# main.net
KiCad netlist of a schematic drawn in EAGLE
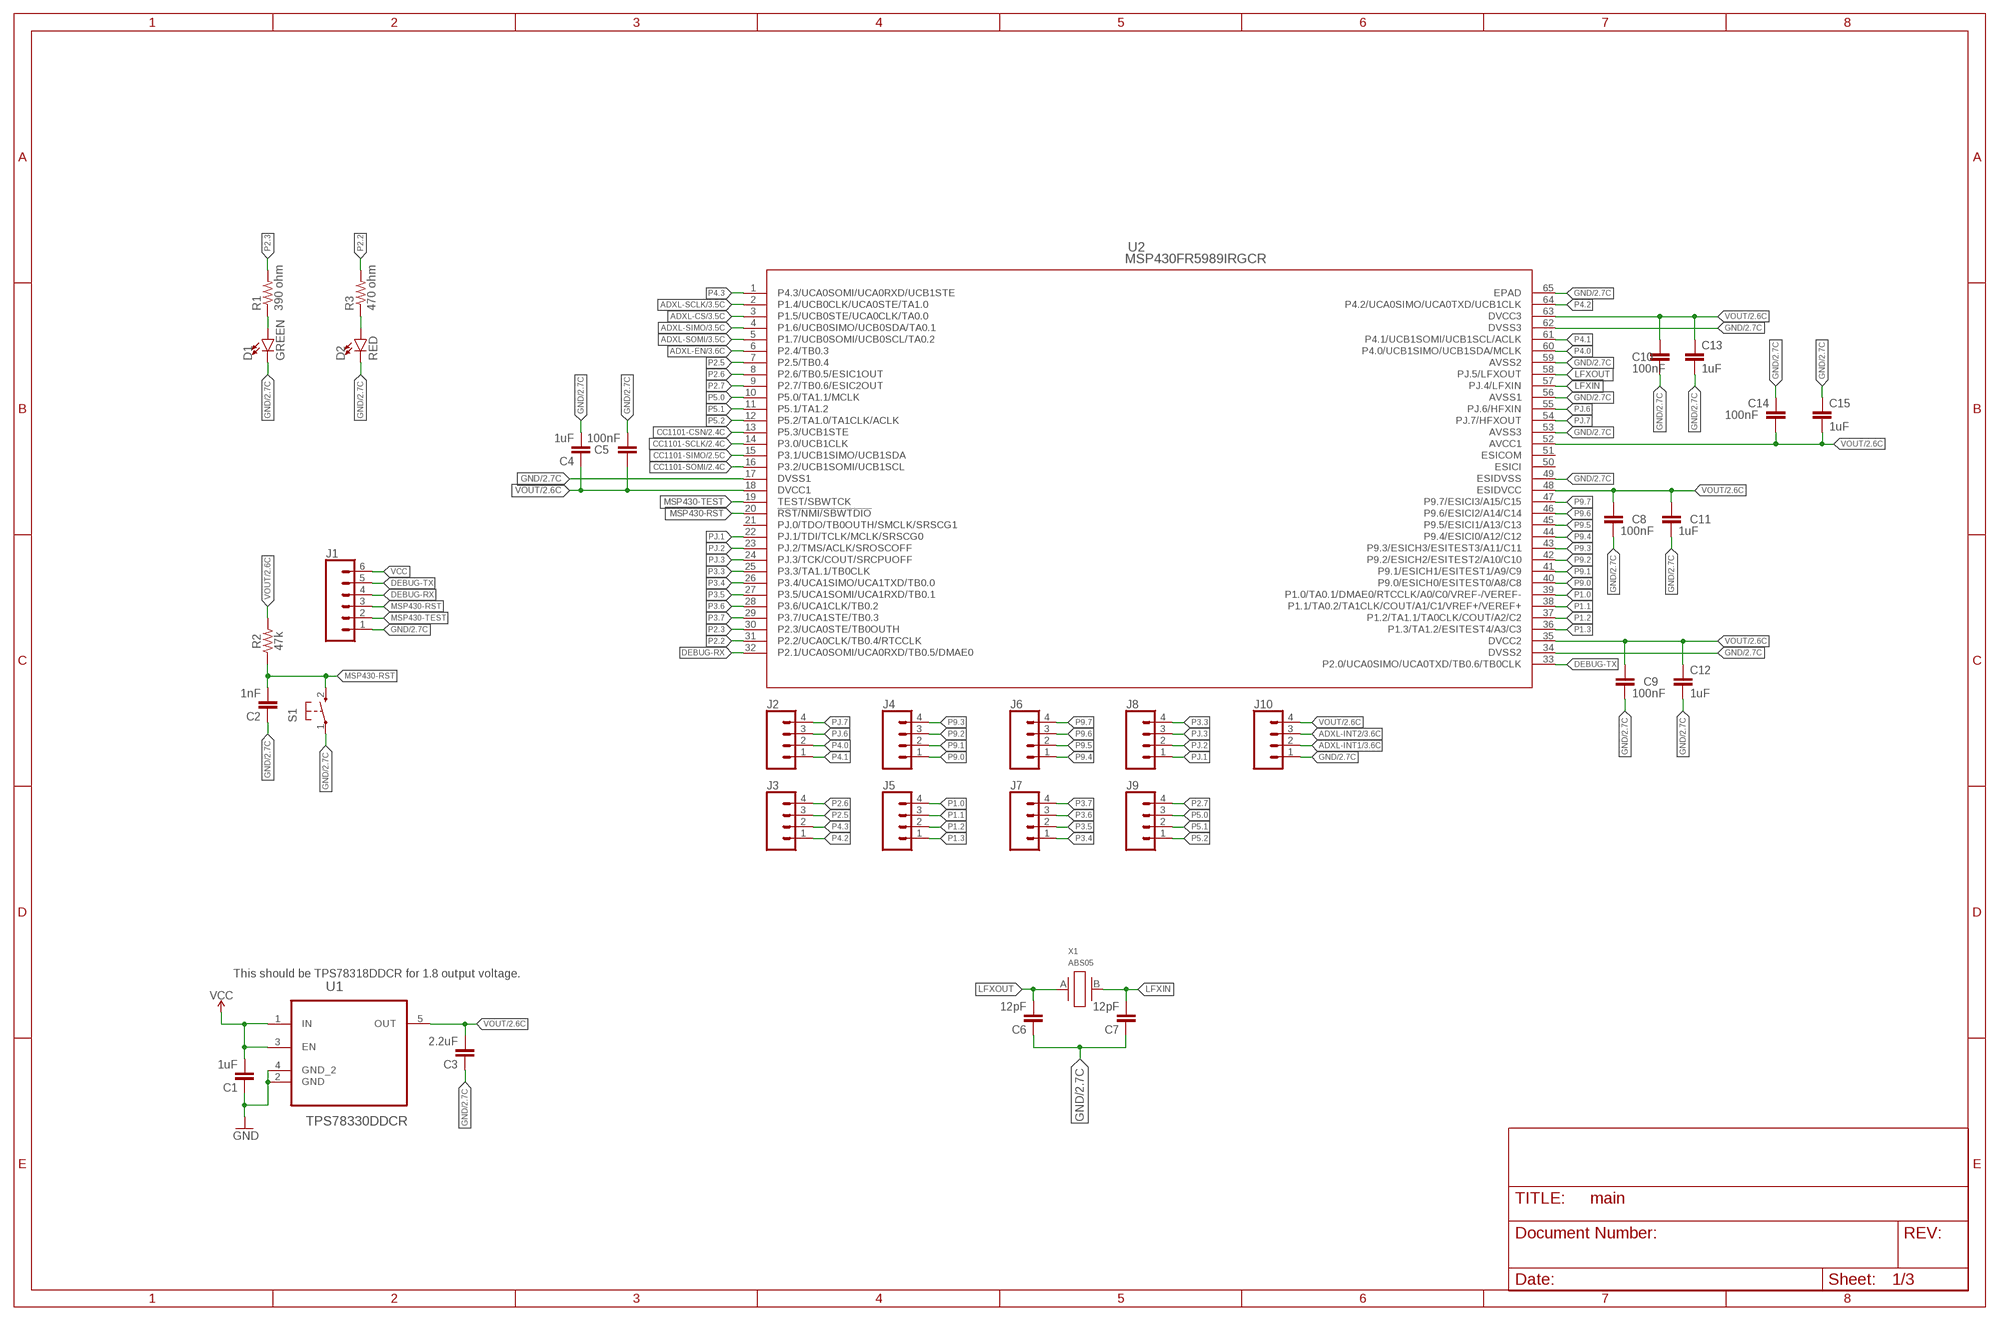
[diagram p0: schematic, sheet 1]
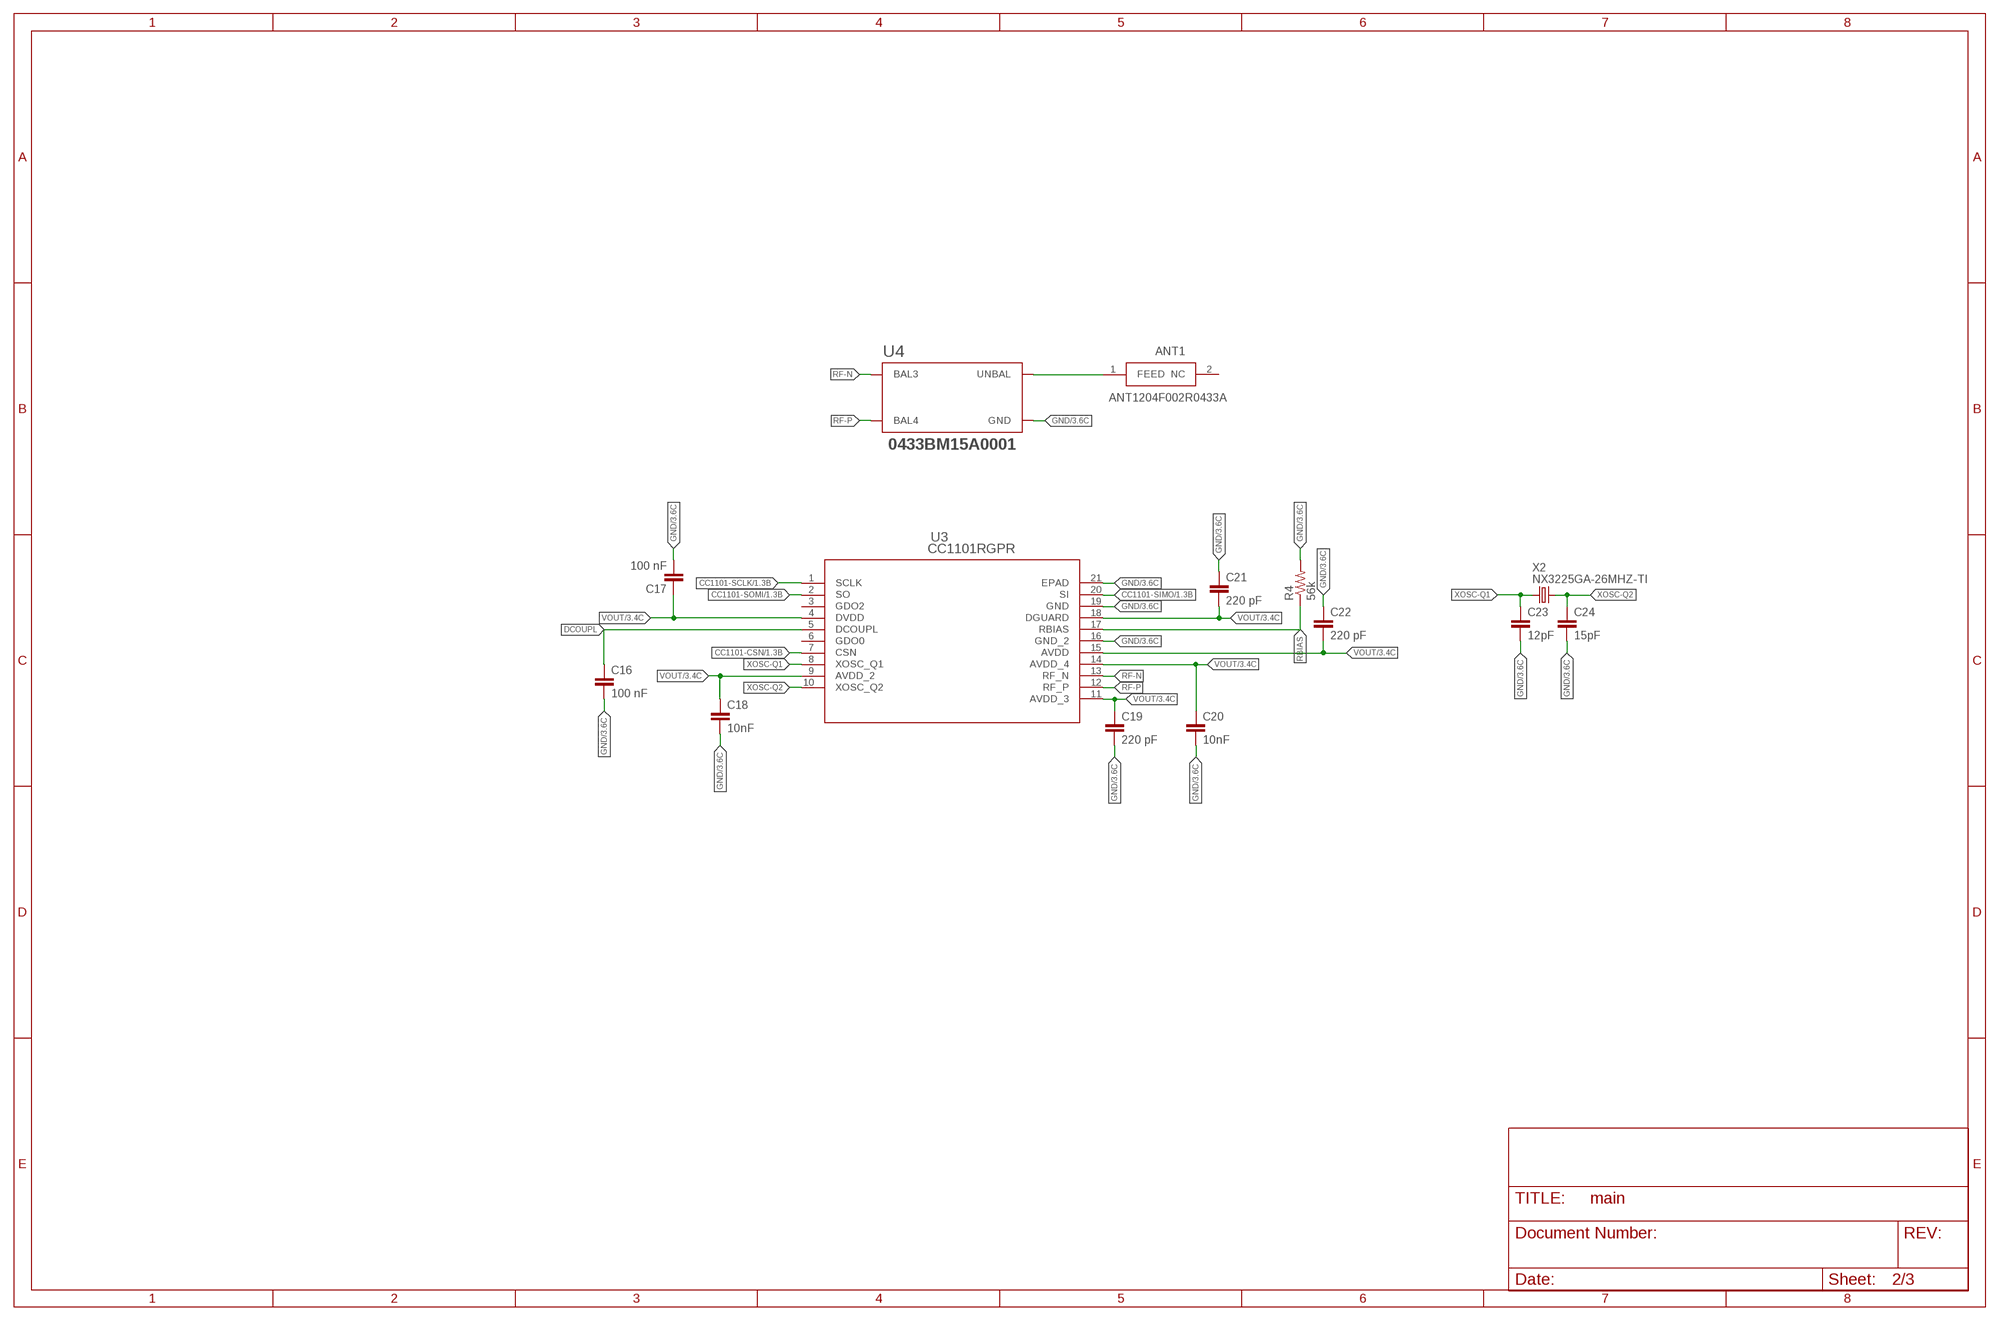
[diagram p1: schematic, sheet 2]
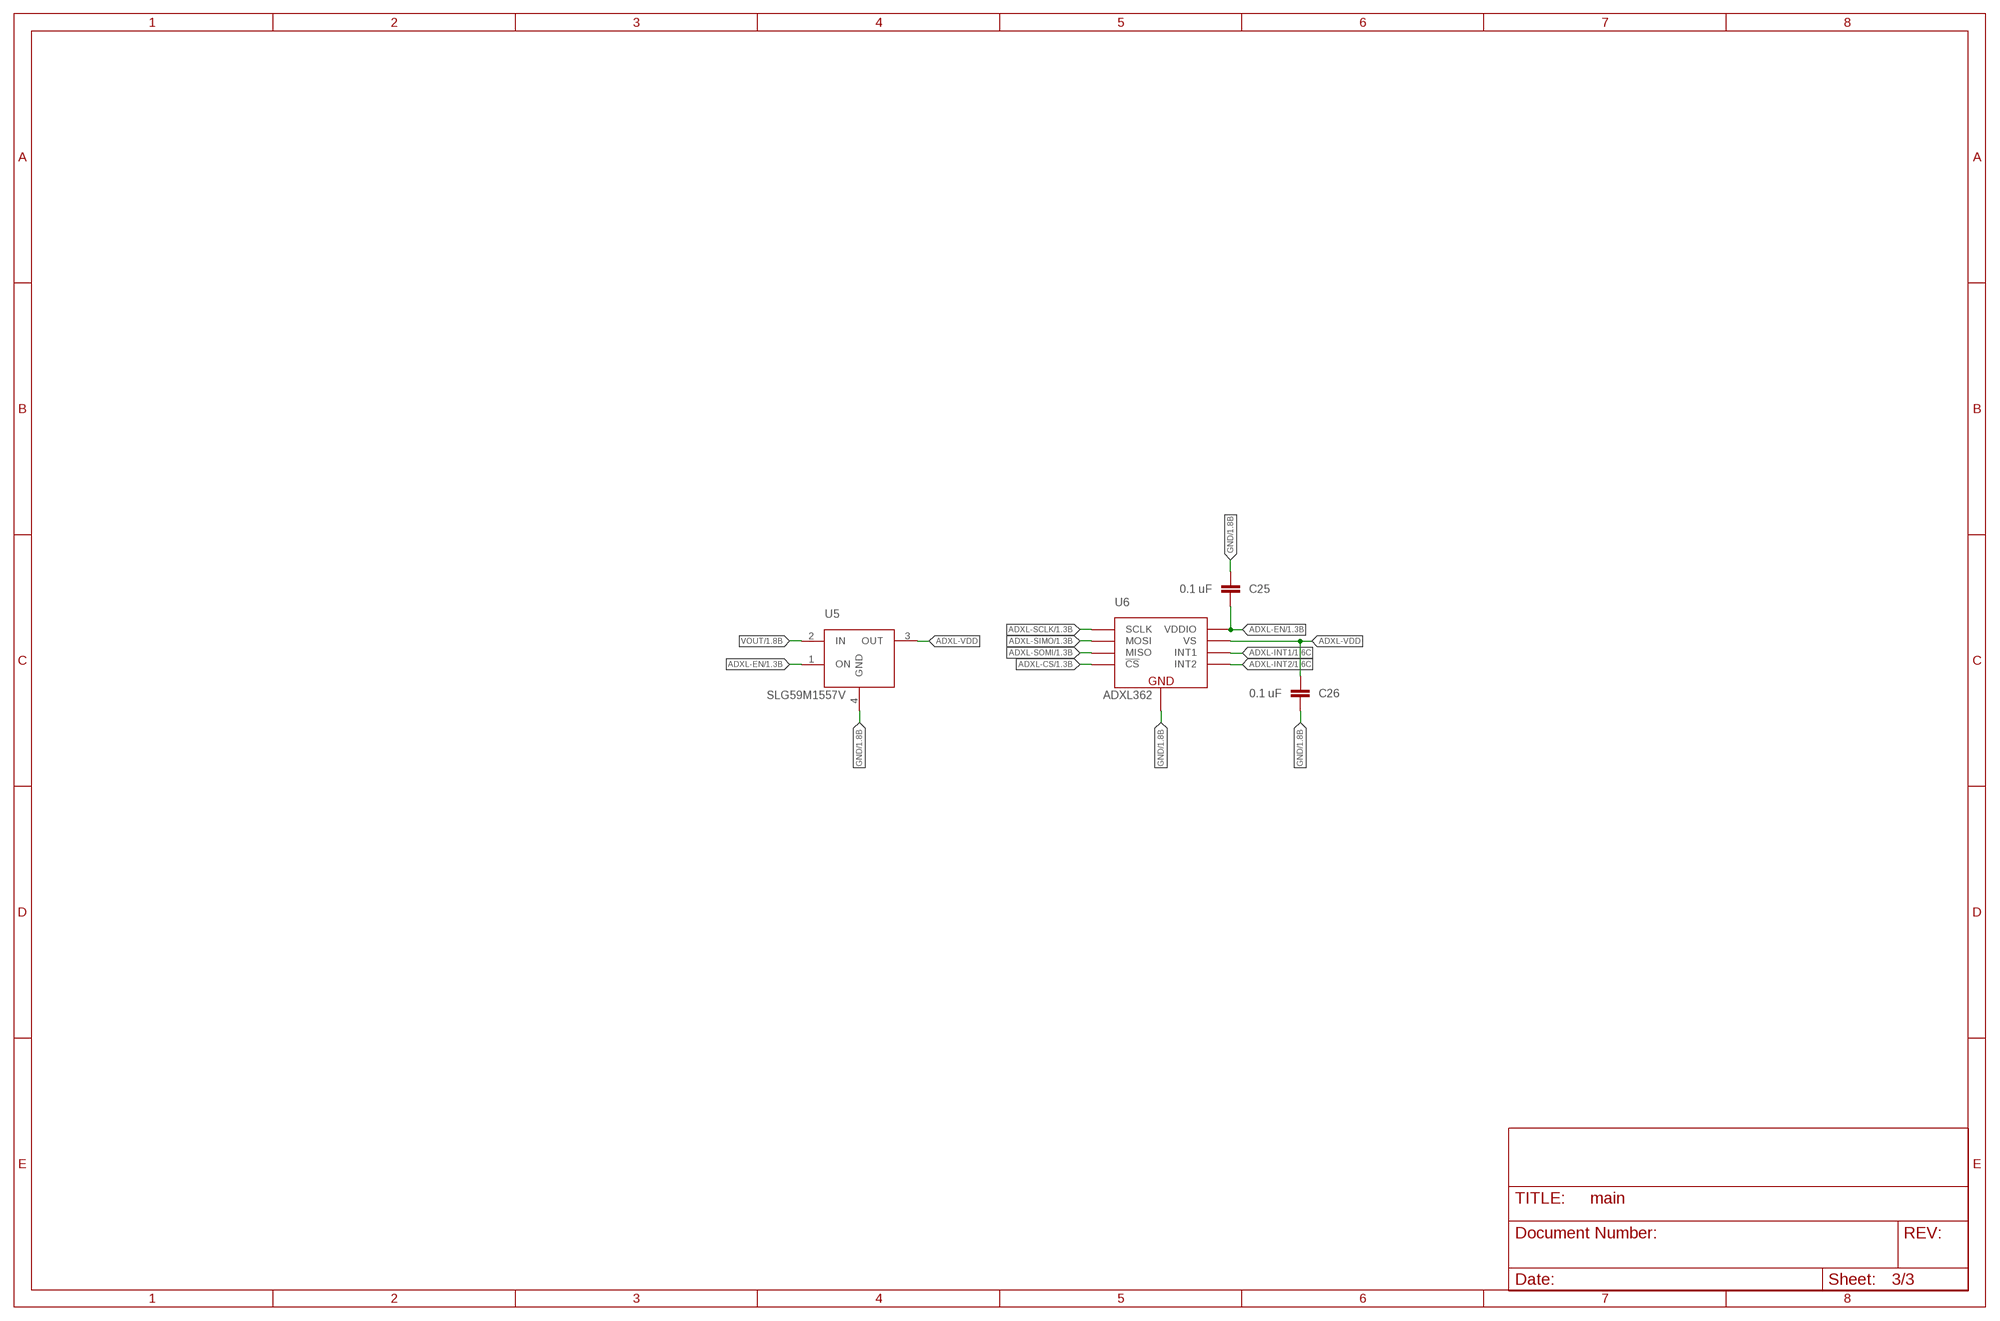
[diagram p2: schematic, sheet 3]

(export (version "E")
  (design (tool "Eeschema 10.0.6"))
  (components
    (comp (ref "C1")
      (value "1uF")
      (footprint "eagle-import:0603")
      (libsource (lib "eagle-import") (part "C-EU0603"))
    )
    (comp (ref "C2")
      (value "1nF")
      (footprint "eagle-import:0603")
      (libsource (lib "eagle-import") (part "C-EU0603"))
    )
    (comp (ref "C3")
      (value "2.2uF")
      (footprint "eagle-import:0603")
      (libsource (lib "eagle-import") (part "C-EU0603"))
    )
    (comp (ref "C4")
      (value "1uF")
      (footprint "eagle-import:0603")
      (libsource (lib "eagle-import") (part "C-EU0603"))
    )
    (comp (ref "C5")
      (value "100nF")
      (footprint "eagle-import:0603")
      (libsource (lib "eagle-import") (part "C-EU0603"))
    )
    (comp (ref "C6")
      (value "12pF")
      (footprint "eagle-import:0603")
      (fields (field (name "MPN") "CL10C120JB8NNNC"))
      (libsource (lib "eagle-import") (part "C-EU0603"))
    )
    (comp (ref "C7")
      (value "12pF")
      (footprint "eagle-import:0603")
      (fields (field (name "MPN") "CL10C120JB8NNNC"))
      (libsource (lib "eagle-import") (part "C-EU0603"))
    )
    (comp (ref "C8")
      (value "100nF")
      (footprint "eagle-import:0603")
      (libsource (lib "eagle-import") (part "C-EU0603"))
    )
    (comp (ref "C9")
      (value "100nF")
      (footprint "eagle-import:0603")
      (libsource (lib "eagle-import") (part "C-EU0603"))
    )
    (comp (ref "C10")
      (value "100nF")
      (footprint "eagle-import:0603")
      (libsource (lib "eagle-import") (part "C-EU0603"))
    )
    (comp (ref "C11")
      (value "1uF")
      (footprint "eagle-import:0603")
      (libsource (lib "eagle-import") (part "C-EU0603"))
    )
    (comp (ref "C12")
      (value "1uF")
      (footprint "eagle-import:0603")
      (libsource (lib "eagle-import") (part "C-EU0603"))
    )
    (comp (ref "C13")
      (value "1uF")
      (footprint "eagle-import:0603")
      (libsource (lib "eagle-import") (part "C-EU0603"))
    )
    (comp (ref "C14")
      (value "100nF")
      (footprint "eagle-import:0603")
      (libsource (lib "eagle-import") (part "C-EU0603"))
    )
    (comp (ref "C15")
      (value "1uF")
      (footprint "eagle-import:0603")
      (libsource (lib "eagle-import") (part "C-EU0603"))
    )
    (comp (ref "D1")
      (value "GREEN")
      (footprint "eagle-import:LED-0603")
      (libsource (lib "eagle-import") (part "LED-GREEN0603"))
    )
    (comp (ref "D2")
      (value "RED")
      (footprint "eagle-import:LED-0603")
      (libsource (lib "eagle-import") (part "LED-RED0603"))
    )
    (comp (ref "J1")
      (value "CONN_06SILK_FEMALE_PTH")
      (footprint "eagle-import:1X06")
      (libsource (lib "eagle-import") (part "CONN_06SILK_FEMALE_PTH"))
    )
    (comp (ref "J2")
      (value "CONN_041.27MM")
      (footprint "eagle-import:1X04_1.27MM")
      (fields (field (name "SPICEPREFIX") "E"))
      (libsource (lib "eagle-import") (part "CONN_041.27MM"))
    )
    (comp (ref "J3")
      (value "CONN_041.27MM")
      (footprint "eagle-import:1X04_1.27MM")
      (fields (field (name "SPICEPREFIX") "E"))
      (libsource (lib "eagle-import") (part "CONN_041.27MM"))
    )
    (comp (ref "J4")
      (value "CONN_041.27MM")
      (footprint "eagle-import:1X04_1.27MM")
      (fields (field (name "SPICEPREFIX") "E"))
      (libsource (lib "eagle-import") (part "CONN_041.27MM"))
    )
    (comp (ref "J5")
      (value "CONN_041.27MM")
      (footprint "eagle-import:1X04_1.27MM")
      (fields (field (name "SPICEPREFIX") "E"))
      (libsource (lib "eagle-import") (part "CONN_041.27MM"))
    )
    (comp (ref "J6")
      (value "CONN_041.27MM")
      (footprint "eagle-import:1X04_1.27MM")
      (fields (field (name "SPICEPREFIX") "E"))
      (libsource (lib "eagle-import") (part "CONN_041.27MM"))
    )
    (comp (ref "J7")
      (value "CONN_041.27MM")
      (footprint "eagle-import:1X04_1.27MM")
      (fields (field (name "SPICEPREFIX") "E"))
      (libsource (lib "eagle-import") (part "CONN_041.27MM"))
    )
    (comp (ref "J8")
      (value "CONN_041.27MM")
      (footprint "eagle-import:1X04_1.27MM")
      (fields (field (name "SPICEPREFIX") "E"))
      (libsource (lib "eagle-import") (part "CONN_041.27MM"))
    )
    (comp (ref "J9")
      (value "CONN_041.27MM")
      (footprint "eagle-import:1X04_1.27MM")
      (fields (field (name "SPICEPREFIX") "E"))
      (libsource (lib "eagle-import") (part "CONN_041.27MM"))
    )
    (comp (ref "J10")
      (value "CONN_041.27MM")
      (footprint "eagle-import:1X04_1.27MM")
      (fields (field (name "SPICEPREFIX") "E"))
      (libsource (lib "eagle-import") (part "CONN_041.27MM"))
    )
    (comp (ref "R1")
      (value "390 ohm")
      (footprint "eagle-import:0402")
      (libsource (lib "eagle-import") (part "R-EU"))
    )
    (comp (ref "R2")
      (value "47k")
      (footprint "eagle-import:0603")
      (libsource (lib "eagle-import") (part "47KOHM-0603-1/10W-1%"))
    )
    (comp (ref "R3")
      (value "470 ohm")
      (footprint "eagle-import:0402")
      (libsource (lib "eagle-import") (part "R-EU"))
    )
    (comp (ref "S1")
      (value "ELECTRICALMETER_PB")
      (footprint "eagle-import:ELECTRICALMETER_PBTH")
      (libsource (lib "eagle-import") (part "ELECTRICALMETER_PB"))
    )
    (comp (ref "U1")
      (value "TPS78330DDCR")
      (footprint "eagle-import:SOT95P280X110-5N")
      (libsource (lib "eagle-import") (part "TPS78330DDCR"))
    )
    (comp (ref "U2")
      (value "MSP430FR5989IRGCR")
      (footprint "eagle-import:RGC64_4P25X4P25")
      (libsource (lib "eagle-import") (part "MSP430FR5989IRGCR"))
    )
    (comp (ref "X1")
      (value "ABS05")
      (footprint "eagle-import:ABS05")
      (fields (field (name "MPN") "ABS05-32.768KHZ-9-T "))
      (libsource (lib "eagle-import") (part "ABS05-32.768KHZ-9-T"))
    )
    (comp (ref "C25")
      (value "0.1 uF")
      (footprint "eagle-import:0603")
      (libsource (lib "eagle-import") (part "C-EU0603"))
    )
    (comp (ref "C26")
      (value "0.1 uF")
      (footprint "eagle-import:0603")
      (libsource (lib "eagle-import") (part "C-EU0603"))
    )
    (comp (ref "U5")
      (value "SLG59M1557V")
      (footprint "eagle-import:4STDFN")
      (fields (field (name "MPN") "SLG59M1557V "))
      (libsource (lib "eagle-import") (part "SLG59M1557V"))
    )
    (comp (ref "U6")
      (value "ADXL362")
      (footprint "eagle-import:ADXL362")
      (fields (field (name "MPN") "ADXL362BCCZ-RL7 "))
      (libsource (lib "eagle-import") (part "ADXL362"))
    )
    (comp (ref "ANT1")
      (value "ANT1204F002R0433A")
      (footprint "eagle-import:ANTC12340X180N")
      (fields (field (name "MOUSER_PART_NUMBER") "603-ANT1204F002R0433"))
      (libsource (lib "eagle-import") (part "ANT1204F002R0433A"))
    )
    (comp (ref "C16")
      (value "100 nF")
      (footprint "eagle-import:0603")
      (fields (field (name "MPN") "GCJ188R71H104KA12D"))
      (libsource (lib "eagle-import") (part "C-EU0603"))
    )
    (comp (ref "C17")
      (value "100 nF")
      (footprint "eagle-import:0603")
      (fields (field (name "MPN") "GCJ188R71H104KA12D"))
      (libsource (lib "eagle-import") (part "C-EU0603"))
    )
    (comp (ref "C18")
      (value "10nF")
      (footprint "eagle-import:0603")
      (fields (field (name "MPN") "GCJ188R71H104KA12D"))
      (libsource (lib "eagle-import") (part "C-EU0603"))
    )
    (comp (ref "C19")
      (value "220 pF")
      (footprint "eagle-import:0603")
      (fields (field (name "MPN") "GCJ188R71H104KA12D"))
      (libsource (lib "eagle-import") (part "C-EU0603"))
    )
    (comp (ref "C20")
      (value "10nF")
      (footprint "eagle-import:0603")
      (fields (field (name "MPN") "GCJ188R71H104KA12D"))
      (libsource (lib "eagle-import") (part "C-EU0603"))
    )
    (comp (ref "C21")
      (value "220 pF")
      (footprint "eagle-import:0603")
      (fields (field (name "MPN") "GCJ188R71H104KA12D"))
      (libsource (lib "eagle-import") (part "C-EU0603"))
    )
    (comp (ref "C22")
      (value "220 pF")
      (footprint "eagle-import:0603")
      (fields (field (name "MPN") "GCJ188R71H104KA12D"))
      (libsource (lib "eagle-import") (part "C-EU0603"))
    )
    (comp (ref "C23")
      (value "12pF")
      (footprint "eagle-import:0603")
      (fields (field (name "MPN") "06035A120FAT2A"))
      (libsource (lib "eagle-import") (part "C-EU0603"))
    )
    (comp (ref "C24")
      (value "15pF")
      (footprint "eagle-import:0603")
      (fields (field (name "MPN") "C1608C0G1H150J080AA"))
      (libsource (lib "eagle-import") (part "C-EU0603"))
    )
    (comp (ref "R4")
      (value "56k")
      (footprint "eagle-import:0603")
      (fields (field (name "MPN") "ERJ-3GEYJ563V"))
      (libsource (lib "eagle-import") (part "R-EU0603"))
    )
    (comp (ref "U3")
      (value "CC1101RGPR")
      (footprint "eagle-import:RGP20_2P4X2P4")
      (libsource (lib "eagle-import") (part "CC1101RGPR"))
    )
    (comp (ref "U4")
      (value "0433BM15A0001")
      (footprint "eagle-import:XXXXBM15A0001")
      (libsource (lib "eagle-import") (part "0433BM15A0001"))
    )
    (comp (ref "X2")
      (value "NX3225GA-26MHZ-TI")
      (footprint "eagle-import:XTAL-3.2X2.5")
      (libsource (lib "eagle-import") (part "XTAL-3.2X2.5"))
    )
  )
  (nets
    (net (code "1") (name "ADXL-CS") (class "Default")
      (node (ref "U2") (pin "3") (pinfunction "P1.5/UCB0STE/UCA0CLK/TA0.0_3") (pintype "bidirectional"))
      (node (ref "U6") (pin "P$8") (pinfunction "~{CS}_P$8") (pintype "bidirectional"))
    )
    (net (code "2") (name "ADXL-EN") (class "Default")
      (node (ref "C25") (pin "1") (pinfunction "1_1") (pintype "passive"))
      (node (ref "U2") (pin "6") (pinfunction "P2.4/TB0.3_6") (pintype "bidirectional"))
      (node (ref "U5") (pin "1") (pinfunction "ON_1") (pintype "bidirectional"))
      (node (ref "U6") (pin "P$1") (pinfunction "VDDIO_P$1") (pintype "bidirectional"))
    )
    (net (code "3") (name "ADXL-INT1") (class "Default")
      (node (ref "J10") (pin "2") (pinfunction "2_2") (pintype "passive"))
      (node (ref "U6") (pin "P$11") (pinfunction "INT1_P$11") (pintype "bidirectional"))
    )
    (net (code "4") (name "ADXL-INT2") (class "Default")
      (node (ref "J10") (pin "3") (pinfunction "3_3") (pintype "passive"))
      (node (ref "U6") (pin "P$9") (pinfunction "INT2_P$9") (pintype "bidirectional"))
    )
    (net (code "5") (name "ADXL-SCLK") (class "Default")
      (node (ref "U2") (pin "2") (pinfunction "P1.4/UCB0CLK/UCA0STE/TA1.0_2") (pintype "bidirectional"))
      (node (ref "U6") (pin "P$4") (pinfunction "SCLK_P$4") (pintype "bidirectional"))
    )
    (net (code "6") (name "ADXL-SIMO") (class "Default")
      (node (ref "U2") (pin "4") (pinfunction "P1.6/UCB0SIMO/UCB0SDA/TA0.1_4") (pintype "bidirectional"))
      (node (ref "U6") (pin "P$6") (pinfunction "MOSI_P$6") (pintype "bidirectional"))
    )
    (net (code "7") (name "ADXL-SOMI") (class "Default")
      (node (ref "U2") (pin "5") (pinfunction "P1.7/UCB0SOMI/UCB0SCL/TA0.2_5") (pintype "bidirectional"))
      (node (ref "U6") (pin "P$7") (pinfunction "MISO_P$7") (pintype "bidirectional"))
    )
    (net (code "8") (name "ADXL-VDD") (class "Default")
      (node (ref "C26") (pin "2") (pinfunction "2_2") (pintype "passive"))
      (node (ref "U5") (pin "3") (pinfunction "OUT_3") (pintype "bidirectional"))
      (node (ref "U6") (pin "P$14") (pinfunction "VS_P$14") (pintype "bidirectional"))
    )
    (net (code "9") (name "CC1101-CSN") (class "Default")
      (node (ref "U2") (pin "13") (pinfunction "P5.3/UCB1STE_13") (pintype "bidirectional"))
      (node (ref "U3") (pin "7") (pinfunction "CSN_7") (pintype "input"))
    )
    (net (code "10") (name "CC1101-SCLK") (class "Default")
      (node (ref "U2") (pin "14") (pinfunction "P3.0/UCB1CLK_14") (pintype "bidirectional"))
      (node (ref "U3") (pin "1") (pinfunction "SCLK_1") (pintype "passive"))
    )
    (net (code "11") (name "CC1101-SIMO") (class "Default")
      (node (ref "U2") (pin "15") (pinfunction "P3.1/UCB1SIMO/UCB1SDA_15") (pintype "bidirectional"))
      (node (ref "U3") (pin "20") (pinfunction "SI_20") (pintype "input"))
    )
    (net (code "12") (name "CC1101-SOMI") (class "Default")
      (node (ref "U2") (pin "16") (pinfunction "P3.2/UCB1SOMI/UCB1SCL_16") (pintype "bidirectional"))
      (node (ref "U3") (pin "2") (pinfunction "SO_2") (pintype "output"))
    )
    (net (code "13") (name "DCOUPL") (class "Default")
      (node (ref "C16") (pin "1") (pinfunction "1_1") (pintype "passive"))
      (node (ref "U3") (pin "5") (pinfunction "DCOUPL_5") (pintype "power_in"))
    )
    (net (code "14") (name "DEBUG-RX") (class "Default")
      (node (ref "J1") (pin "4") (pinfunction "4_4") (pintype "passive"))
      (node (ref "U2") (pin "32") (pinfunction "P2.1/UCA0SOMI/UCA0RXD/TB0.5/DMAE0_32") (pintype "bidirectional"))
    )
    (net (code "15") (name "DEBUG-TX") (class "Default")
      (node (ref "J1") (pin "5") (pinfunction "5_5") (pintype "passive"))
      (node (ref "U2") (pin "33") (pinfunction "P2.0/UCA0SIMO/UCA0TXD/TB0.6/TB0CLK_33") (pintype "bidirectional"))
    )
    (net (code "16") (name "GND") (class "Default")
      (node (ref "C1") (pin "1") (pinfunction "1_1") (pintype "passive"))
      (node (ref "C10") (pin "2") (pinfunction "2_2") (pintype "passive"))
      (node (ref "C11") (pin "2") (pinfunction "2_2") (pintype "passive"))
      (node (ref "C12") (pin "2") (pinfunction "2_2") (pintype "passive"))
      (node (ref "C13") (pin "2") (pinfunction "2_2") (pintype "passive"))
      (node (ref "C14") (pin "1") (pinfunction "1_1") (pintype "passive"))
      (node (ref "C15") (pin "1") (pinfunction "1_1") (pintype "passive"))
      (node (ref "C16") (pin "2") (pinfunction "2_2") (pintype "passive"))
      (node (ref "C17") (pin "2") (pinfunction "2_2") (pintype "passive"))
      (node (ref "C18") (pin "2") (pinfunction "2_2") (pintype "passive"))
      (node (ref "C19") (pin "2") (pinfunction "2_2") (pintype "passive"))
      (node (ref "C2") (pin "1") (pinfunction "1_1") (pintype "passive"))
      (node (ref "C20") (pin "2") (pinfunction "2_2") (pintype "passive"))
      (node (ref "C21") (pin "1") (pinfunction "1_1") (pintype "passive"))
      (node (ref "C22") (pin "1") (pinfunction "1_1") (pintype "passive"))
      (node (ref "C23") (pin "2") (pinfunction "2_2") (pintype "passive"))
      (node (ref "C24") (pin "2") (pinfunction "2_2") (pintype "passive"))
      (node (ref "C25") (pin "2") (pinfunction "2_2") (pintype "passive"))
      (node (ref "C26") (pin "1") (pinfunction "1_1") (pintype "passive"))
      (node (ref "C3") (pin "1") (pinfunction "1_1") (pintype "passive"))
      (node (ref "C4") (pin "2") (pinfunction "2_2") (pintype "passive"))
      (node (ref "C5") (pin "2") (pinfunction "2_2") (pintype "passive"))
      (node (ref "C6") (pin "1") (pinfunction "1_1") (pintype "passive"))
      (node (ref "C7") (pin "1") (pinfunction "1_1") (pintype "passive"))
      (node (ref "C8") (pin "2") (pinfunction "2_2") (pintype "passive"))
      (node (ref "C9") (pin "2") (pinfunction "2_2") (pintype "passive"))
      (node (ref "D1") (pin "C") (pinfunction "C_C") (pintype "passive"))
      (node (ref "D2") (pin "C") (pinfunction "C_C") (pintype "passive"))
      (node (ref "J1") (pin "1") (pinfunction "1_1") (pintype "passive"))
      (node (ref "J10") (pin "1") (pinfunction "1_1") (pintype "passive"))
      (node (ref "R4") (pin "2") (pinfunction "2_2") (pintype "passive"))
      (node (ref "S1") (pin "1") (pinfunction "P_1") (pintype "passive"))
      (node (ref "U1") (pin "2") (pinfunction "GND_2") (pintype "passive"))
      (node (ref "U1") (pin "4") (pinfunction "GND_2_4") (pintype "passive"))
      (node (ref "U2") (pin "17") (pinfunction "DVSS1_17") (pintype "power_in"))
      (node (ref "U2") (pin "34") (pinfunction "DVSS2_34") (pintype "power_in"))
      (node (ref "U2") (pin "49") (pinfunction "ESIDVSS_49") (pintype "power_in"))
      (node (ref "U2") (pin "53") (pinfunction "AVSS3_53") (pintype "power_in"))
      (node (ref "U2") (pin "56") (pinfunction "AVSS1_56") (pintype "power_in"))
      (node (ref "U2") (pin "59") (pinfunction "AVSS2_59") (pintype "power_in"))
      (node (ref "U2") (pin "62") (pinfunction "DVSS3_62") (pintype "power_in"))
      (node (ref "U2") (pin "65") (pinfunction "EPAD_65") (pintype "passive"))
      (node (ref "U3") (pin "16") (pinfunction "GND_2_16") (pintype "power_in"))
      (node (ref "U3") (pin "19") (pinfunction "GND_19") (pintype "power_in"))
      (node (ref "U3") (pin "21") (pinfunction "EPAD_21") (pintype "power_in"))
      (node (ref "U4") (pin "2") (pinfunction "GND_2") (pintype "bidirectional"))
      (node (ref "U4") (pin "5") (pinfunction "GND_5") (pintype "bidirectional"))
      (node (ref "U4") (pin "6") (pinfunction "GND_6") (pintype "bidirectional"))
      (node (ref "U5") (pin "4") (pinfunction "GND_4") (pintype "bidirectional"))
      (node (ref "U6") (pin "P$12") (pinfunction "GND_P$12") (pintype "bidirectional"))
      (node (ref "U6") (pin "P$13") (pinfunction "GND_P$13") (pintype "bidirectional"))
      (node (ref "U6") (pin "P$16") (pinfunction "GND_P$16") (pintype "bidirectional"))
    )
    (net (code "17") (name "LFXIN") (class "Default")
      (node (ref "C7") (pin "2") (pinfunction "2_2") (pintype "passive"))
      (node (ref "U2") (pin "57") (pinfunction "PJ.4/LFXIN_57") (pintype "bidirectional"))
      (node (ref "X1") (pin "B") (pinfunction "2_B") (pintype "bidirectional"))
    )
    (net (code "18") (name "LFXOUT") (class "Default")
      (node (ref "C6") (pin "2") (pinfunction "2_2") (pintype "passive"))
      (node (ref "U2") (pin "58") (pinfunction "PJ.5/LFXOUT_58") (pintype "bidirectional"))
      (node (ref "X1") (pin "A") (pinfunction "1_A") (pintype "bidirectional"))
    )
    (net (code "19") (name "MSP430-RST") (class "Default")
      (node (ref "C2") (pin "2") (pinfunction "2_2") (pintype "passive"))
      (node (ref "J1") (pin "3") (pinfunction "3_3") (pintype "passive"))
      (node (ref "R2") (pin "1") (pinfunction "1_1") (pintype "passive"))
      (node (ref "S1") (pin "2") (pinfunction "S_2") (pintype "passive"))
      (node (ref "U2") (pin "20") (pinfunction "~{RST/NMI/SBWTDIO}_20") (pintype "bidirectional"))
    )
    (net (code "20") (name "MSP430-TEST") (class "Default")
      (node (ref "J1") (pin "2") (pinfunction "2_2") (pintype "passive"))
      (node (ref "U2") (pin "19") (pinfunction "TEST/SBWTCK_19") (pintype "input"))
    )
    (net (code "21") (name "Net-(ANT1-FEED)") (class "Default")
      (node (ref "ANT1") (pin "1") (pinfunction "FEED_1") (pintype "input"))
      (node (ref "U4") (pin "1") (pinfunction "UNBAL_1") (pintype "bidirectional"))
    )
    (net (code "22") (name "Net-(D1-PadA)") (class "Default")
      (node (ref "D1") (pin "A") (pinfunction "A_A") (pintype "passive"))
      (node (ref "R1") (pin "1") (pinfunction "1_1") (pintype "passive"))
    )
    (net (code "23") (name "Net-(D2-PadA)") (class "Default")
      (node (ref "D2") (pin "A") (pinfunction "A_A") (pintype "passive"))
      (node (ref "R3") (pin "1") (pinfunction "1_1") (pintype "passive"))
    )
    (net (code "24") (name "P1.0") (class "Default")
      (node (ref "J5") (pin "4") (pinfunction "4_4") (pintype "passive"))
      (node (ref "U2") (pin "39") (pinfunction "P1.0/TA0.1/DMAE0/RTCCLK/A0/C0/VREF-/VEREF-_39") (pintype "bidirectional"))
    )
    (net (code "25") (name "P1.1") (class "Default")
      (node (ref "J5") (pin "3") (pinfunction "3_3") (pintype "passive"))
      (node (ref "U2") (pin "38") (pinfunction "P1.1/TA0.2/TA1CLK/COUT/A1/C1/VREF+/VEREF+_38") (pintype "bidirectional"))
    )
    (net (code "26") (name "P1.2") (class "Default")
      (node (ref "J5") (pin "2") (pinfunction "2_2") (pintype "passive"))
      (node (ref "U2") (pin "37") (pinfunction "P1.2/TA1.1/TA0CLK/COUT/A2/C2_37") (pintype "bidirectional"))
    )
    (net (code "27") (name "P1.3") (class "Default")
      (node (ref "J5") (pin "1") (pinfunction "1_1") (pintype "passive"))
      (node (ref "U2") (pin "36") (pinfunction "P1.3/TA1.2/ESITEST4/A3/C3_36") (pintype "bidirectional"))
    )
    (net (code "28") (name "P2.2") (class "Default")
      (node (ref "R3") (pin "2") (pinfunction "2_2") (pintype "passive"))
      (node (ref "U2") (pin "31") (pinfunction "P2.2/UCA0CLK/TB0.4/RTCCLK_31") (pintype "bidirectional"))
    )
    (net (code "29") (name "P2.3") (class "Default")
      (node (ref "R1") (pin "2") (pinfunction "2_2") (pintype "passive"))
      (node (ref "U2") (pin "30") (pinfunction "P2.3/UCA0STE/TB0OUTH_30") (pintype "bidirectional"))
    )
    (net (code "30") (name "P2.5") (class "Default")
      (node (ref "J3") (pin "3") (pinfunction "3_3") (pintype "passive"))
      (node (ref "U2") (pin "7") (pinfunction "P2.5/TB0.4_7") (pintype "bidirectional"))
    )
    (net (code "31") (name "P2.6") (class "Default")
      (node (ref "J3") (pin "4") (pinfunction "4_4") (pintype "passive"))
      (node (ref "U2") (pin "8") (pinfunction "P2.6/TB0.5/ESIC1OUT_8") (pintype "bidirectional"))
    )
    (net (code "32") (name "P2.7") (class "Default")
      (node (ref "J9") (pin "4") (pinfunction "4_4") (pintype "passive"))
      (node (ref "U2") (pin "9") (pinfunction "P2.7/TB0.6/ESIC2OUT_9") (pintype "bidirectional"))
    )
    (net (code "33") (name "P3.3") (class "Default")
      (node (ref "J8") (pin "4") (pinfunction "4_4") (pintype "passive"))
      (node (ref "U2") (pin "25") (pinfunction "P3.3/TA1.1/TB0CLK_25") (pintype "bidirectional"))
    )
    (net (code "34") (name "P3.4") (class "Default")
      (node (ref "J7") (pin "1") (pinfunction "1_1") (pintype "passive"))
      (node (ref "U2") (pin "26") (pinfunction "P3.4/UCA1SIMO/UCA1TXD/TB0.0_26") (pintype "bidirectional"))
    )
    (net (code "35") (name "P3.5") (class "Default")
      (node (ref "J7") (pin "2") (pinfunction "2_2") (pintype "passive"))
      (node (ref "U2") (pin "27") (pinfunction "P3.5/UCA1SOMI/UCA1RXD/TB0.1_27") (pintype "bidirectional"))
    )
    (net (code "36") (name "P3.6") (class "Default")
      (node (ref "J7") (pin "3") (pinfunction "3_3") (pintype "passive"))
      (node (ref "U2") (pin "28") (pinfunction "P3.6/UCA1CLK/TB0.2_28") (pintype "bidirectional"))
    )
    (net (code "37") (name "P3.7") (class "Default")
      (node (ref "J7") (pin "4") (pinfunction "4_4") (pintype "passive"))
      (node (ref "U2") (pin "29") (pinfunction "P3.7/UCA1STE/TB0.3_29") (pintype "bidirectional"))
    )
    (net (code "38") (name "P4.0") (class "Default")
      (node (ref "J2") (pin "2") (pinfunction "2_2") (pintype "passive"))
      (node (ref "U2") (pin "60") (pinfunction "P4.0/UCB1SIMO/UCB1SDA/MCLK_60") (pintype "bidirectional"))
    )
    (net (code "39") (name "P4.1") (class "Default")
      (node (ref "J2") (pin "1") (pinfunction "1_1") (pintype "passive"))
      (node (ref "U2") (pin "61") (pinfunction "P4.1/UCB1SOMI/UCB1SCL/ACLK_61") (pintype "bidirectional"))
    )
    (net (code "40") (name "P4.2") (class "Default")
      (node (ref "J3") (pin "1") (pinfunction "1_1") (pintype "passive"))
      (node (ref "U2") (pin "64") (pinfunction "P4.2/UCA0SIMO/UCA0TXD/UCB1CLK_64") (pintype "bidirectional"))
    )
    (net (code "41") (name "P4.3") (class "Default")
      (node (ref "J3") (pin "2") (pinfunction "2_2") (pintype "passive"))
      (node (ref "U2") (pin "1") (pinfunction "P4.3/UCA0SOMI/UCA0RXD/UCB1STE_1") (pintype "bidirectional"))
    )
    (net (code "42") (name "P5.0") (class "Default")
      (node (ref "J9") (pin "3") (pinfunction "3_3") (pintype "passive"))
      (node (ref "U2") (pin "10") (pinfunction "P5.0/TA1.1/MCLK_10") (pintype "bidirectional"))
    )
    (net (code "43") (name "P5.1") (class "Default")
      (node (ref "J9") (pin "2") (pinfunction "2_2") (pintype "passive"))
      (node (ref "U2") (pin "11") (pinfunction "P5.1/TA1.2_11") (pintype "bidirectional"))
    )
    (net (code "44") (name "P5.2") (class "Default")
      (node (ref "J9") (pin "1") (pinfunction "1_1") (pintype "passive"))
      (node (ref "U2") (pin "12") (pinfunction "P5.2/TA1.0/TA1CLK/ACLK_12") (pintype "bidirectional"))
    )
    (net (code "45") (name "P9.0") (class "Default")
      (node (ref "J4") (pin "1") (pinfunction "1_1") (pintype "passive"))
      (node (ref "U2") (pin "40") (pinfunction "P9.0/ESICH0/ESITEST0/A8/C8_40") (pintype "bidirectional"))
    )
    (net (code "46") (name "P9.1") (class "Default")
      (node (ref "J4") (pin "2") (pinfunction "2_2") (pintype "passive"))
      (node (ref "U2") (pin "41") (pinfunction "P9.1/ESICH1/ESITEST1/A9/C9_41") (pintype "bidirectional"))
    )
    (net (code "47") (name "P9.2") (class "Default")
      (node (ref "J4") (pin "3") (pinfunction "3_3") (pintype "passive"))
      (node (ref "U2") (pin "42") (pinfunction "P9.2/ESICH2/ESITEST2/A10/C10_42") (pintype "bidirectional"))
    )
    (net (code "48") (name "P9.3") (class "Default")
      (node (ref "J4") (pin "4") (pinfunction "4_4") (pintype "passive"))
      (node (ref "U2") (pin "43") (pinfunction "P9.3/ESICH3/ESITEST3/A11/C11_43") (pintype "bidirectional"))
    )
    (net (code "49") (name "P9.4") (class "Default")
      (node (ref "J6") (pin "1") (pinfunction "1_1") (pintype "passive"))
      (node (ref "U2") (pin "44") (pinfunction "P9.4/ESICI0/A12/C12_44") (pintype "bidirectional"))
    )
    (net (code "50") (name "P9.5") (class "Default")
      (node (ref "J6") (pin "2") (pinfunction "2_2") (pintype "passive"))
      (node (ref "U2") (pin "45") (pinfunction "P9.5/ESICI1/A13/C13_45") (pintype "bidirectional"))
    )
    (net (code "51") (name "P9.6") (class "Default")
      (node (ref "J6") (pin "3") (pinfunction "3_3") (pintype "passive"))
      (node (ref "U2") (pin "46") (pinfunction "P9.6/ESICI2/A14/C14_46") (pintype "bidirectional"))
    )
    (net (code "52") (name "P9.7") (class "Default")
      (node (ref "J6") (pin "4") (pinfunction "4_4") (pintype "passive"))
      (node (ref "U2") (pin "47") (pinfunction "P9.7/ESICI3/A15/C15_47") (pintype "bidirectional"))
    )
    (net (code "53") (name "PJ.1") (class "Default")
      (node (ref "J8") (pin "1") (pinfunction "1_1") (pintype "passive"))
      (node (ref "U2") (pin "22") (pinfunction "PJ.1/TDI/TCLK/MCLK/SRSCG0_22") (pintype "bidirectional"))
    )
    (net (code "54") (name "PJ.2") (class "Default")
      (node (ref "J8") (pin "2") (pinfunction "2_2") (pintype "passive"))
      (node (ref "U2") (pin "23") (pinfunction "PJ.2/TMS/ACLK/SROSCOFF_23") (pintype "bidirectional"))
    )
    (net (code "55") (name "PJ.3") (class "Default")
      (node (ref "J8") (pin "3") (pinfunction "3_3") (pintype "passive"))
      (node (ref "U2") (pin "24") (pinfunction "PJ.3/TCK/COUT/SRCPUOFF_24") (pintype "bidirectional"))
    )
    (net (code "56") (name "PJ.6") (class "Default")
      (node (ref "J2") (pin "3") (pinfunction "3_3") (pintype "passive"))
      (node (ref "U2") (pin "55") (pinfunction "PJ.6/HFXIN_55") (pintype "bidirectional"))
    )
    (net (code "57") (name "PJ.7") (class "Default")
      (node (ref "J2") (pin "4") (pinfunction "4_4") (pintype "passive"))
      (node (ref "U2") (pin "54") (pinfunction "PJ.7/HFXOUT_54") (pintype "bidirectional"))
    )
    (net (code "58") (name "RBIAS") (class "Default")
      (node (ref "R4") (pin "1") (pinfunction "1_1") (pintype "passive"))
      (node (ref "U3") (pin "17") (pinfunction "RBIAS_17") (pintype "bidirectional"))
    )
    (net (code "59") (name "RF-N") (class "Default")
      (node (ref "U3") (pin "13") (pinfunction "RF_N_13") (pintype "bidirectional"))
      (node (ref "U4") (pin "3") (pinfunction "BAL3_3") (pintype "bidirectional"))
    )
    (net (code "60") (name "RF-P") (class "Default")
      (node (ref "U3") (pin "12") (pinfunction "RF_P_12") (pintype "bidirectional"))
      (node (ref "U4") (pin "4") (pinfunction "BAL4_4") (pintype "bidirectional"))
    )
    (net (code "61") (name "VCC") (class "Default")
      (node (ref "C1") (pin "2") (pinfunction "2_2") (pintype "passive"))
      (node (ref "J1") (pin "6") (pinfunction "6_6") (pintype "passive"))
      (node (ref "U1") (pin "1") (pinfunction "IN_1") (pintype "input"))
      (node (ref "U1") (pin "3") (pinfunction "EN_3") (pintype "input"))
    )
    (net (code "62") (name "VOUT") (class "Default")
      (node (ref "C10") (pin "1") (pinfunction "1_1") (pintype "passive"))
      (node (ref "C11") (pin "1") (pinfunction "1_1") (pintype "passive"))
      (node (ref "C12") (pin "1") (pinfunction "1_1") (pintype "passive"))
      (node (ref "C13") (pin "1") (pinfunction "1_1") (pintype "passive"))
      (node (ref "C14") (pin "2") (pinfunction "2_2") (pintype "passive"))
      (node (ref "C15") (pin "2") (pinfunction "2_2") (pintype "passive"))
      (node (ref "C17") (pin "1") (pinfunction "1_1") (pintype "passive"))
      (node (ref "C18") (pin "1") (pinfunction "1_1") (pintype "passive"))
      (node (ref "C19") (pin "1") (pinfunction "1_1") (pintype "passive"))
      (node (ref "C20") (pin "1") (pinfunction "1_1") (pintype "passive"))
      (node (ref "C21") (pin "2") (pinfunction "2_2") (pintype "passive"))
      (node (ref "C22") (pin "2") (pinfunction "2_2") (pintype "passive"))
      (node (ref "C3") (pin "2") (pinfunction "2_2") (pintype "passive"))
      (node (ref "C4") (pin "1") (pinfunction "1_1") (pintype "passive"))
      (node (ref "C5") (pin "1") (pinfunction "1_1") (pintype "passive"))
      (node (ref "C8") (pin "1") (pinfunction "1_1") (pintype "passive"))
      (node (ref "C9") (pin "1") (pinfunction "1_1") (pintype "passive"))
      (node (ref "J10") (pin "4") (pinfunction "4_4") (pintype "passive"))
      (node (ref "R2") (pin "2") (pinfunction "2_2") (pintype "passive"))
      (node (ref "U1") (pin "5") (pinfunction "OUT_5") (pintype "output"))
      (node (ref "U2") (pin "18") (pinfunction "DVCC1_18") (pintype "power_in"))
      (node (ref "U2") (pin "35") (pinfunction "DVCC2_35") (pintype "power_in"))
      (node (ref "U2") (pin "48") (pinfunction "ESIDVCC_48") (pintype "power_in"))
      (node (ref "U2") (pin "52") (pinfunction "AVCC1_52") (pintype "power_in"))
      (node (ref "U2") (pin "63") (pinfunction "DVCC3_63") (pintype "power_in"))
      (node (ref "U3") (pin "11") (pinfunction "AVDD_3_11") (pintype "power_in"))
      (node (ref "U3") (pin "14") (pinfunction "AVDD_4_14") (pintype "power_in"))
      (node (ref "U3") (pin "15") (pinfunction "AVDD_15") (pintype "power_in"))
      (node (ref "U3") (pin "18") (pinfunction "DGUARD_18") (pintype "power_in"))
      (node (ref "U3") (pin "4") (pinfunction "DVDD_4") (pintype "power_in"))
      (node (ref "U3") (pin "9") (pinfunction "AVDD_2_9") (pintype "power_in"))
      (node (ref "U5") (pin "2") (pinfunction "IN_2") (pintype "bidirectional"))
    )
    (net (code "63") (name "XOSC-Q1") (class "Default")
      (node (ref "C23") (pin "1") (pinfunction "1_1") (pintype "passive"))
      (node (ref "U3") (pin "8") (pinfunction "XOSC_Q1_8") (pintype "bidirectional"))
      (node (ref "X2") (pin "1") (pinfunction "1_1") (pintype "passive"))
    )
    (net (code "64") (name "XOSC-Q2") (class "Default")
      (node (ref "C24") (pin "1") (pinfunction "1_1") (pintype "passive"))
      (node (ref "U3") (pin "10") (pinfunction "XOSC_Q2_10") (pintype "bidirectional"))
      (node (ref "X2") (pin "3") (pinfunction "2_3") (pintype "passive"))
    )
    (net (code "65") (name "unconnected-(ANT1-NC-Pad2)") (class "Default")
      (node (ref "ANT1") (pin "2") (pinfunction "NC_2") (pintype "no_connect"))
    )
    (net (code "66") (name "unconnected-(U2-ESICI-Pad50)") (class "Default")
      (node (ref "U2") (pin "50") (pinfunction "ESICI_50") (pintype "input"))
    )
    (net (code "67") (name "unconnected-(U2-ESICOM-Pad51)") (class "Default")
      (node (ref "U2") (pin "51") (pinfunction "ESICOM_51") (pintype "passive"))
    )
    (net (code "68") (name "unconnected-(U2-PJ.0{slash}TDO{slash}TB0OUTH{slash}SMCLK{slash}SRSCG1-Pad21)") (class "Default")
      (node (ref "U2") (pin "21") (pinfunction "PJ.0/TDO/TB0OUTH/SMCLK/SRSCG1_21") (pintype "bidirectional"))
    )
    (net (code "69") (name "unconnected-(U3-GDO0-Pad6)") (class "Default")
      (node (ref "U3") (pin "6") (pinfunction "GDO0_6") (pintype "bidirectional"))
    )
    (net (code "70") (name "unconnected-(U3-GDO2-Pad3)") (class "Default")
      (node (ref "U3") (pin "3") (pinfunction "GDO2_3") (pintype "output"))
    )
  )
)
